# GPIO.net
KiCad netlist of a schematic drawn in EAGLE
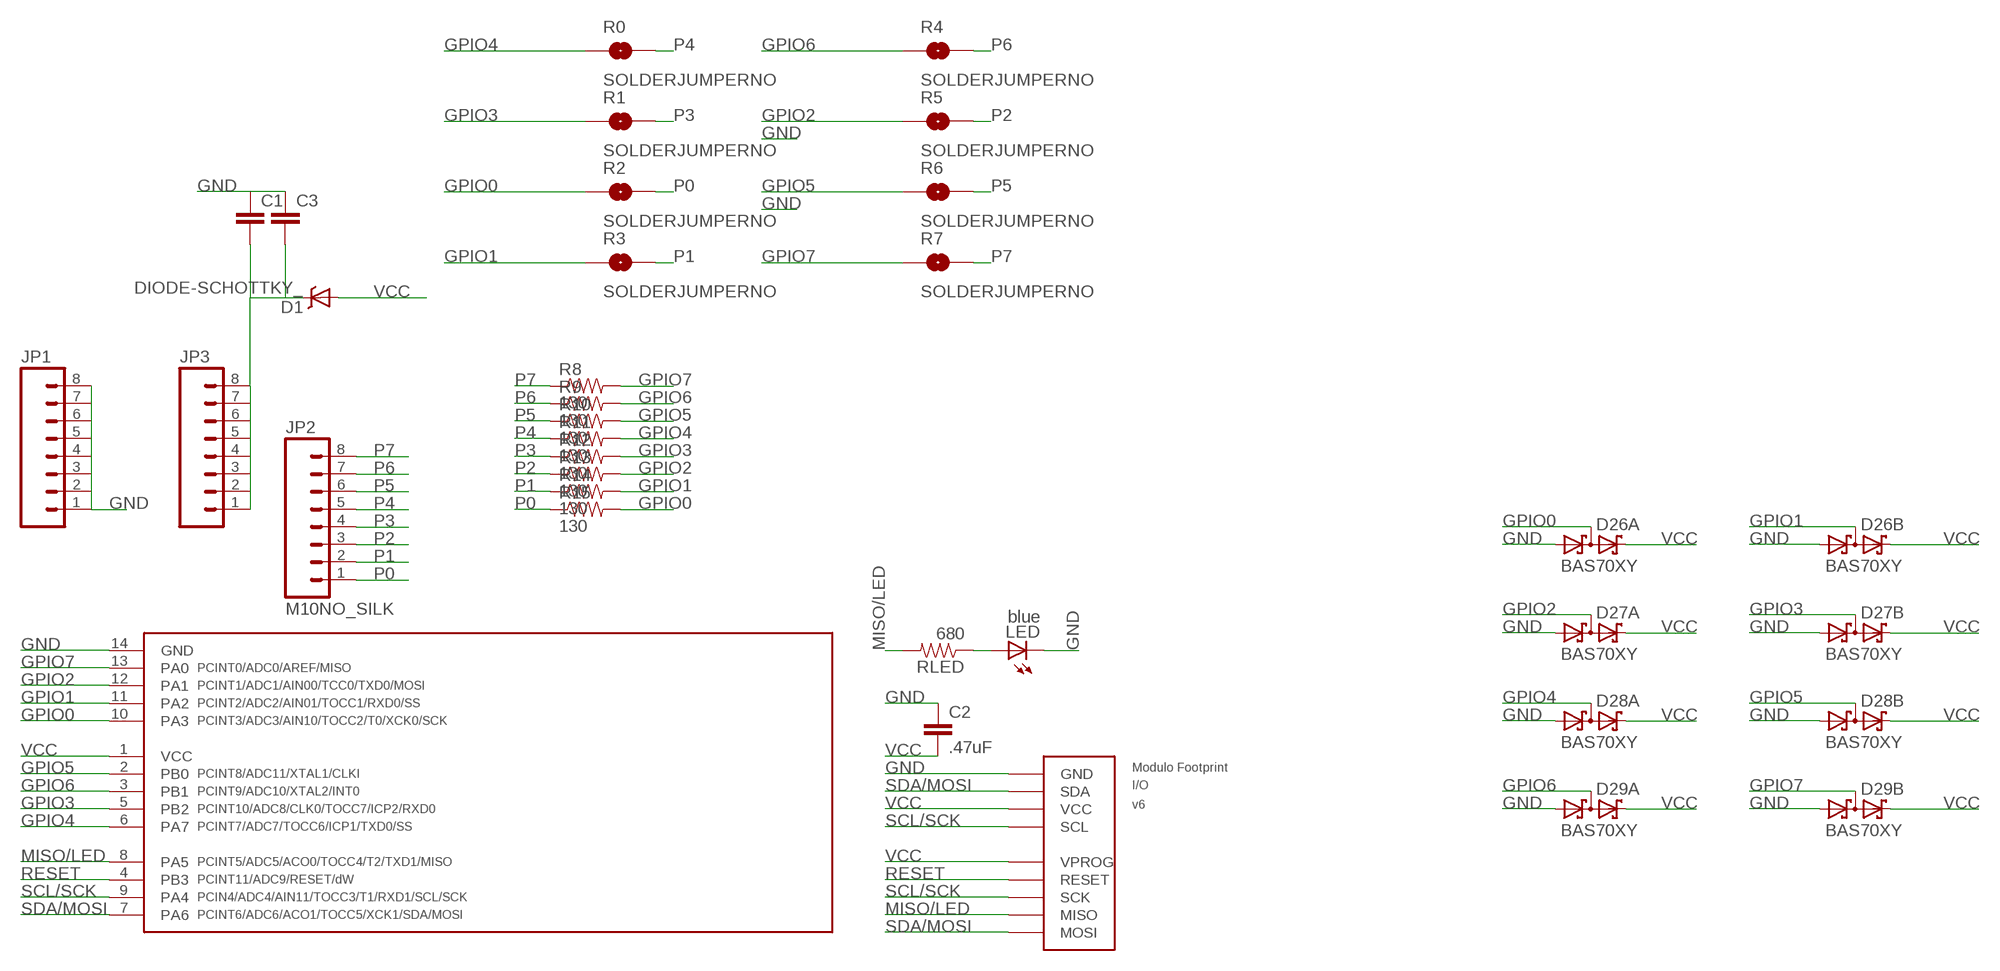
[diagram p0: schematic, sheet 1]

(export (version "E")
  (design (tool "Eeschema 10.0.6"))
  (components
    (comp (ref "C1")
      (value "CAP1206")
      (footprint "eagle-import:1206")
      (libsource (lib "eagle-import") (part "CAP1206"))
    )
    (comp (ref "C2")
      (value ".47uF")
      (footprint "eagle-import:0805")
      (libsource (lib "eagle-import") (part "CAP0805"))
    )
    (comp (ref "C3")
      (value "CAP1206")
      (footprint "eagle-import:1206")
      (libsource (lib "eagle-import") (part "CAP1206"))
    )
    (comp (ref "D1")
      (value "DIODE-SCHOTTKY_")
      (footprint "eagle-import:SMA-DIODE")
      (libsource (lib "eagle-import") (part "DIODE-SCHOTTKY_"))
    )
    (comp (ref "D26")
      (value "BAS70XY")
      (footprint "eagle-import:SOT363_PHILIPS")
      (libsource (lib "eagle-import") (part "BAS70XY"))
    )
    (comp (ref "D27")
      (value "BAS70XY")
      (footprint "eagle-import:SOT363_PHILIPS")
      (libsource (lib "eagle-import") (part "BAS70XY"))
    )
    (comp (ref "D28")
      (value "BAS70XY")
      (footprint "eagle-import:SOT363_PHILIPS")
      (libsource (lib "eagle-import") (part "BAS70XY"))
    )
    (comp (ref "D29")
      (value "BAS70XY")
      (footprint "eagle-import:SOT363_PHILIPS")
      (libsource (lib "eagle-import") (part "BAS70XY"))
    )
    (comp (ref "JP1")
      (value "M08NO_SILK")
      (footprint "eagle-import:1X08_NO_SILK")
      (libsource (lib "eagle-import") (part "M08NO_SILK"))
    )
    (comp (ref "JP2")
      (value "M10NO_SILK")
      (footprint "eagle-import:1X08_NO_SILK")
      (libsource (lib "eagle-import") (part "M08NO_SILK"))
    )
    (comp (ref "JP3")
      (value "M08NO_SILK")
      (footprint "eagle-import:1X08_NO_SILK")
      (libsource (lib "eagle-import") (part "M08NO_SILK"))
    )
    (comp (ref "LED")
      (value "blue")
      (footprint "eagle-import:CHIPLED_0805")
      (libsource (lib "eagle-import") (part "LEDCHIPLED_0805"))
    )
    (comp (ref "R0")
      (value "SOLDERJUMPERNO")
      (footprint "eagle-import:SJ_2S-NO")
      (libsource (lib "eagle-import") (part "SOLDERJUMPERNO"))
    )
    (comp (ref "R1")
      (value "SOLDERJUMPERNO")
      (footprint "eagle-import:SJ_2S-NO")
      (libsource (lib "eagle-import") (part "SOLDERJUMPERNO"))
    )
    (comp (ref "R2")
      (value "SOLDERJUMPERNO")
      (footprint "eagle-import:SJ_2S-NO")
      (libsource (lib "eagle-import") (part "SOLDERJUMPERNO"))
    )
    (comp (ref "R3")
      (value "SOLDERJUMPERNO")
      (footprint "eagle-import:SJ_2S-NO")
      (libsource (lib "eagle-import") (part "SOLDERJUMPERNO"))
    )
    (comp (ref "R4")
      (value "SOLDERJUMPERNO")
      (footprint "eagle-import:SJ_2S-NO")
      (libsource (lib "eagle-import") (part "SOLDERJUMPERNO"))
    )
    (comp (ref "R5")
      (value "SOLDERJUMPERNO")
      (footprint "eagle-import:SJ_2S-NO")
      (libsource (lib "eagle-import") (part "SOLDERJUMPERNO"))
    )
    (comp (ref "R6")
      (value "SOLDERJUMPERNO")
      (footprint "eagle-import:SJ_2S-NO")
      (libsource (lib "eagle-import") (part "SOLDERJUMPERNO"))
    )
    (comp (ref "R7")
      (value "SOLDERJUMPERNO")
      (footprint "eagle-import:SJ_2S-NO")
      (libsource (lib "eagle-import") (part "SOLDERJUMPERNO"))
    )
    (comp (ref "R8")
      (value "130")
      (footprint "eagle-import:0805")
      (libsource (lib "eagle-import") (part "SparkFun-Resistors_RESISTOR0805-RES"))
    )
    (comp (ref "R9")
      (value "130")
      (footprint "eagle-import:0805")
      (libsource (lib "eagle-import") (part "SparkFun-Resistors_RESISTOR0805-RES"))
    )
    (comp (ref "R10")
      (value "130")
      (footprint "eagle-import:0805")
      (libsource (lib "eagle-import") (part "SparkFun-Resistors_RESISTOR0805-RES"))
    )
    (comp (ref "R11")
      (value "130")
      (footprint "eagle-import:0805")
      (libsource (lib "eagle-import") (part "SparkFun-Resistors_RESISTOR0805-RES"))
    )
    (comp (ref "R12")
      (value "130")
      (footprint "eagle-import:0805")
      (libsource (lib "eagle-import") (part "SparkFun-Resistors_RESISTOR0805-RES"))
    )
    (comp (ref "R13")
      (value "130")
      (footprint "eagle-import:0805")
      (libsource (lib "eagle-import") (part "SparkFun-Resistors_RESISTOR0805-RES"))
    )
    (comp (ref "R14")
      (value "130")
      (footprint "eagle-import:0805")
      (libsource (lib "eagle-import") (part "SparkFun-Resistors_RESISTOR0805-RES"))
    )
    (comp (ref "R15")
      (value "130")
      (footprint "eagle-import:0805")
      (libsource (lib "eagle-import") (part "SparkFun-Resistors_RESISTOR0805-RES"))
    )
    (comp (ref "RLED")
      (value "680")
      (footprint "eagle-import:0805")
      (libsource (lib "eagle-import") (part "RESISTOR0805-RES"))
    )
    (comp (ref "U$3")
      (value "TINY841")
      (footprint "eagle-import:SOIC14")
      (libsource (lib "eagle-import") (part "TINY841"))
    )
    (comp (ref "U$4")
      (value "FOOTPRINTFOOTPRINT-2")
      (footprint "eagle-import:FOOTPRINT2")
      (fields (field (name "BOARD") "I/O") (field (name "VERSION") "v6"))
      (libsource (lib "eagle-import") (part "FOOTPRINTFOOTPRINT-2"))
    )
  )
  (nets
    (net (code "1") (name "/GND") (class "Default")
      (node (ref "C1") (pin "1") (pinfunction "1_1") (pintype "passive"))
      (node (ref "C2") (pin "1") (pinfunction "1_1") (pintype "passive"))
      (node (ref "C3") (pin "1") (pinfunction "1_1") (pintype "passive"))
      (node (ref "D26") (pin "1") (pinfunction "A1_1") (pintype "passive"))
      (node (ref "D26") (pin "4") (pinfunction "A1_4") (pintype "passive"))
      (node (ref "D27") (pin "1") (pinfunction "A1_1") (pintype "passive"))
      (node (ref "D27") (pin "4") (pinfunction "A1_4") (pintype "passive"))
      (node (ref "D28") (pin "1") (pinfunction "A1_1") (pintype "passive"))
      (node (ref "D28") (pin "4") (pinfunction "A1_4") (pintype "passive"))
      (node (ref "D29") (pin "1") (pinfunction "A1_1") (pintype "passive"))
      (node (ref "D29") (pin "4") (pinfunction "A1_4") (pintype "passive"))
      (node (ref "JP1") (pin "1") (pinfunction "1_1") (pintype "passive"))
      (node (ref "JP1") (pin "2") (pinfunction "2_2") (pintype "passive"))
      (node (ref "JP1") (pin "3") (pinfunction "3_3") (pintype "passive"))
      (node (ref "JP1") (pin "4") (pinfunction "4_4") (pintype "passive"))
      (node (ref "JP1") (pin "5") (pinfunction "5_5") (pintype "passive"))
      (node (ref "JP1") (pin "6") (pinfunction "6_6") (pintype "passive"))
      (node (ref "JP1") (pin "7") (pinfunction "7_7") (pintype "passive"))
      (node (ref "JP1") (pin "8") (pinfunction "8_8") (pintype "passive"))
      (node (ref "LED") (pin "C") (pinfunction "C_C") (pintype "passive"))
      (node (ref "U$3") (pin "14") (pinfunction "GND_14") (pintype "bidirectional"))
      (node (ref "U$4") (pin "BUS0") (pinfunction "GND_BUS0") (pintype "bidirectional"))
    )
    (net (code "2") (name "/GPIO0") (class "Default")
      (node (ref "D26") (pin "6") (pinfunction "C1A2_6") (pintype "passive"))
      (node (ref "R15") (pin "2") (pinfunction "2_2") (pintype "passive"))
      (node (ref "R2") (pin "1") (pinfunction "1_1") (pintype "passive"))
      (node (ref "U$3") (pin "10") (pinfunction "PA3_10") (pintype "bidirectional"))
    )
    (net (code "3") (name "/GPIO1") (class "Default")
      (node (ref "D26") (pin "3") (pinfunction "C1A2_3") (pintype "passive"))
      (node (ref "R14") (pin "2") (pinfunction "2_2") (pintype "passive"))
      (node (ref "R3") (pin "1") (pinfunction "1_1") (pintype "passive"))
      (node (ref "U$3") (pin "11") (pinfunction "PA2_11") (pintype "bidirectional"))
    )
    (net (code "4") (name "/GPIO2") (class "Default")
      (node (ref "D27") (pin "6") (pinfunction "C1A2_6") (pintype "passive"))
      (node (ref "R13") (pin "2") (pinfunction "2_2") (pintype "passive"))
      (node (ref "R5") (pin "1") (pinfunction "1_1") (pintype "passive"))
      (node (ref "U$3") (pin "12") (pinfunction "PA1_12") (pintype "bidirectional"))
    )
    (net (code "5") (name "/GPIO3") (class "Default")
      (node (ref "D27") (pin "3") (pinfunction "C1A2_3") (pintype "passive"))
      (node (ref "R1") (pin "1") (pinfunction "1_1") (pintype "passive"))
      (node (ref "R12") (pin "2") (pinfunction "2_2") (pintype "passive"))
      (node (ref "U$3") (pin "5") (pinfunction "PB2_5") (pintype "bidirectional"))
    )
    (net (code "6") (name "/GPIO4") (class "Default")
      (node (ref "D28") (pin "6") (pinfunction "C1A2_6") (pintype "passive"))
      (node (ref "R0") (pin "1") (pinfunction "1_1") (pintype "passive"))
      (node (ref "R11") (pin "2") (pinfunction "2_2") (pintype "passive"))
      (node (ref "U$3") (pin "6") (pinfunction "PA7_6") (pintype "bidirectional"))
    )
    (net (code "7") (name "/GPIO5") (class "Default")
      (node (ref "D28") (pin "3") (pinfunction "C1A2_3") (pintype "passive"))
      (node (ref "R10") (pin "2") (pinfunction "2_2") (pintype "passive"))
      (node (ref "R6") (pin "1") (pinfunction "1_1") (pintype "passive"))
      (node (ref "U$3") (pin "2") (pinfunction "PB0_2") (pintype "bidirectional"))
    )
    (net (code "8") (name "/GPIO6") (class "Default")
      (node (ref "D29") (pin "6") (pinfunction "C1A2_6") (pintype "passive"))
      (node (ref "R4") (pin "1") (pinfunction "1_1") (pintype "passive"))
      (node (ref "R9") (pin "2") (pinfunction "2_2") (pintype "passive"))
      (node (ref "U$3") (pin "3") (pinfunction "PB1_3") (pintype "bidirectional"))
    )
    (net (code "9") (name "/GPIO7") (class "Default")
      (node (ref "D29") (pin "3") (pinfunction "C1A2_3") (pintype "passive"))
      (node (ref "R7") (pin "1") (pinfunction "1_1") (pintype "passive"))
      (node (ref "R8") (pin "2") (pinfunction "2_2") (pintype "passive"))
      (node (ref "U$3") (pin "13") (pinfunction "PA0_13") (pintype "bidirectional"))
    )
    (net (code "10") (name "/MISO{slash}LED") (class "Default")
      (node (ref "RLED") (pin "2") (pinfunction "2_2") (pintype "passive"))
      (node (ref "U$3") (pin "8") (pinfunction "PA5_8") (pintype "bidirectional"))
      (node (ref "U$4") (pin "PROG3") (pinfunction "MISO_PROG3") (pintype "bidirectional"))
    )
    (net (code "11") (name "/P0") (class "Default")
      (node (ref "JP2") (pin "1") (pinfunction "1_1") (pintype "passive"))
      (node (ref "R15") (pin "1") (pinfunction "1_1") (pintype "passive"))
      (node (ref "R2") (pin "2") (pinfunction "2_2") (pintype "passive"))
    )
    (net (code "12") (name "/P1") (class "Default")
      (node (ref "JP2") (pin "2") (pinfunction "2_2") (pintype "passive"))
      (node (ref "R14") (pin "1") (pinfunction "1_1") (pintype "passive"))
      (node (ref "R3") (pin "2") (pinfunction "2_2") (pintype "passive"))
    )
    (net (code "13") (name "/P2") (class "Default")
      (node (ref "JP2") (pin "3") (pinfunction "3_3") (pintype "passive"))
      (node (ref "R13") (pin "1") (pinfunction "1_1") (pintype "passive"))
      (node (ref "R5") (pin "2") (pinfunction "2_2") (pintype "passive"))
    )
    (net (code "14") (name "/P3") (class "Default")
      (node (ref "JP2") (pin "4") (pinfunction "4_4") (pintype "passive"))
      (node (ref "R1") (pin "2") (pinfunction "2_2") (pintype "passive"))
      (node (ref "R12") (pin "1") (pinfunction "1_1") (pintype "passive"))
    )
    (net (code "15") (name "/P4") (class "Default")
      (node (ref "JP2") (pin "5") (pinfunction "5_5") (pintype "passive"))
      (node (ref "R0") (pin "2") (pinfunction "2_2") (pintype "passive"))
      (node (ref "R11") (pin "1") (pinfunction "1_1") (pintype "passive"))
    )
    (net (code "16") (name "/P5") (class "Default")
      (node (ref "JP2") (pin "6") (pinfunction "6_6") (pintype "passive"))
      (node (ref "R10") (pin "1") (pinfunction "1_1") (pintype "passive"))
      (node (ref "R6") (pin "2") (pinfunction "2_2") (pintype "passive"))
    )
    (net (code "17") (name "/P6") (class "Default")
      (node (ref "JP2") (pin "7") (pinfunction "7_7") (pintype "passive"))
      (node (ref "R4") (pin "2") (pinfunction "2_2") (pintype "passive"))
      (node (ref "R9") (pin "1") (pinfunction "1_1") (pintype "passive"))
    )
    (net (code "18") (name "/P7") (class "Default")
      (node (ref "JP2") (pin "8") (pinfunction "8_8") (pintype "passive"))
      (node (ref "R7") (pin "2") (pinfunction "2_2") (pintype "passive"))
      (node (ref "R8") (pin "1") (pinfunction "1_1") (pintype "passive"))
    )
    (net (code "19") (name "/RESET") (class "Default")
      (node (ref "U$3") (pin "4") (pinfunction "PB3_4") (pintype "bidirectional"))
      (node (ref "U$4") (pin "PROG1") (pinfunction "RESET_PROG1") (pintype "bidirectional"))
    )
    (net (code "20") (name "/SCL{slash}SCK") (class "Default")
      (node (ref "U$3") (pin "9") (pinfunction "PA4_9") (pintype "bidirectional"))
      (node (ref "U$4") (pin "BUS3") (pinfunction "SCL_BUS3") (pintype "bidirectional"))
      (node (ref "U$4") (pin "PROG2") (pinfunction "SCK_PROG2") (pintype "bidirectional"))
    )
    (net (code "21") (name "/SDA{slash}MOSI") (class "Default")
      (node (ref "U$3") (pin "7") (pinfunction "PA6_7") (pintype "bidirectional"))
      (node (ref "U$4") (pin "BUS1") (pinfunction "SDA_BUS1") (pintype "bidirectional"))
      (node (ref "U$4") (pin "PROG4") (pinfunction "MOSI_PROG4") (pintype "bidirectional"))
    )
    (net (code "22") (name "/VCC") (class "Default")
      (node (ref "C2") (pin "2") (pinfunction "2_2") (pintype "passive"))
      (node (ref "D1") (pin "A") (pinfunction "A_A") (pintype "passive"))
      (node (ref "D26") (pin "2") (pinfunction "C2_2") (pintype "passive"))
      (node (ref "D26") (pin "5") (pinfunction "C2_5") (pintype "passive"))
      (node (ref "D27") (pin "2") (pinfunction "C2_2") (pintype "passive"))
      (node (ref "D27") (pin "5") (pinfunction "C2_5") (pintype "passive"))
      (node (ref "D28") (pin "2") (pinfunction "C2_2") (pintype "passive"))
      (node (ref "D28") (pin "5") (pinfunction "C2_5") (pintype "passive"))
      (node (ref "D29") (pin "2") (pinfunction "C2_2") (pintype "passive"))
      (node (ref "D29") (pin "5") (pinfunction "C2_5") (pintype "passive"))
      (node (ref "U$3") (pin "1") (pinfunction "VCC_1") (pintype "bidirectional"))
      (node (ref "U$4") (pin "BUS2") (pinfunction "VCC_BUS2") (pintype "bidirectional"))
      (node (ref "U$4") (pin "PROG0") (pinfunction "VPROG_PROG0") (pintype "bidirectional"))
    )
    (net (code "23") (name "Net-(C1-Pad2)") (class "Default")
      (node (ref "C1") (pin "2") (pinfunction "2_2") (pintype "passive"))
      (node (ref "C3") (pin "2") (pinfunction "2_2") (pintype "passive"))
      (node (ref "D1") (pin "C") (pinfunction "C_C") (pintype "passive"))
      (node (ref "JP3") (pin "1") (pinfunction "1_1") (pintype "passive"))
      (node (ref "JP3") (pin "2") (pinfunction "2_2") (pintype "passive"))
      (node (ref "JP3") (pin "3") (pinfunction "3_3") (pintype "passive"))
      (node (ref "JP3") (pin "4") (pinfunction "4_4") (pintype "passive"))
      (node (ref "JP3") (pin "5") (pinfunction "5_5") (pintype "passive"))
      (node (ref "JP3") (pin "6") (pinfunction "6_6") (pintype "passive"))
      (node (ref "JP3") (pin "7") (pinfunction "7_7") (pintype "passive"))
      (node (ref "JP3") (pin "8") (pinfunction "8_8") (pintype "passive"))
    )
    (net (code "24") (name "Net-(LED-PadA)") (class "Default")
      (node (ref "LED") (pin "A") (pinfunction "A_A") (pintype "passive"))
      (node (ref "RLED") (pin "1") (pinfunction "1_1") (pintype "passive"))
    )
  )
)
